# Serial.net
KiCad netlist of a schematic drawn in Altium Designer
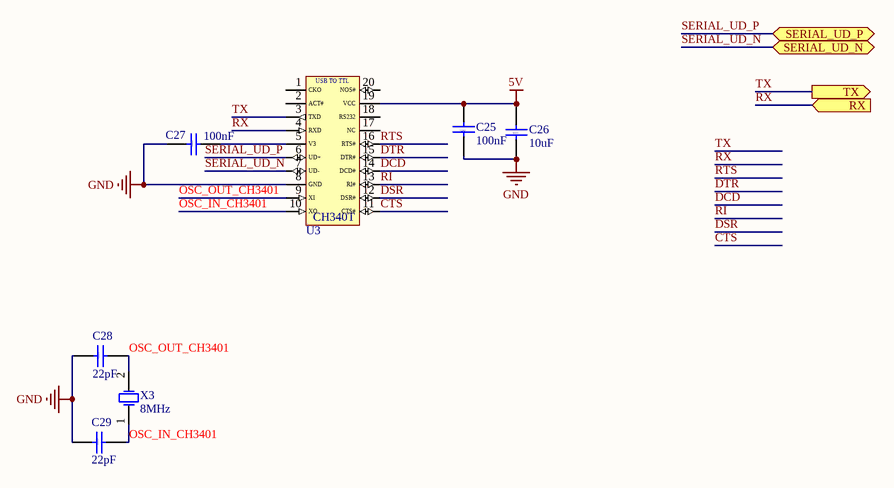
[diagram p0: Serial.SchDoc]

(export (version "E")
  (design (tool "Eeschema 10.0.6"))
  (components
    (comp (ref "C25")
      (value "100nF")
      (footprint "RES 0805")
      (libsource (lib "Full lib F.kh-V2") (part "CAP 0805"))
    )
    (comp (ref "C26")
      (value "10uF")
      (footprint "Res 1206")
      (libsource (lib "Full lib F.kh-V2") (part "CAP 1206"))
    )
    (comp (ref "C27")
      (value "100nF")
      (footprint "RES 0805")
      (libsource (lib "Full lib F.kh-V2") (part "CAP 0805"))
    )
    (comp (ref "C28")
      (value "22pF")
      (footprint "RES 0805")
      (libsource (lib "Full lib F.kh-V2") (part "CAP 0805"))
    )
    (comp (ref "C29")
      (value "22pF")
      (footprint "RES 0805")
      (libsource (lib "Full lib F.kh-V2") (part "CAP 0805"))
    )
    (comp (ref "U3")
      (value "CH340")
      (footprint "SSOP20")
      (description "USB to serial chip CH340")
      (libsource (lib "Full lib F.kh-V2") (part "CH340T"))
    )
    (comp (ref "X3")
      (value "8MHz")
      (footprint "XTAL - SMD")
      (libsource (lib "Full lib F.kh-V2") (part "XTAL - SMD"))
    )
  )
  (nets
    (net (code "1") (name "/CTS") (class "Default")
      (node (ref "U3") (pin "11") (pinfunction "CTS#_11") (pintype "bidirectional"))
    )
    (net (code "2") (name "/DCD") (class "Default")
      (node (ref "U3") (pin "14") (pinfunction "DCD#_14") (pintype "bidirectional"))
    )
    (net (code "3") (name "/DSR") (class "Default")
      (node (ref "U3") (pin "12") (pinfunction "DSR#_12") (pintype "bidirectional"))
    )
    (net (code "4") (name "/DTR") (class "Default")
      (node (ref "U3") (pin "15") (pinfunction "DTR#_15") (pintype "bidirectional"))
    )
    (net (code "5") (name "/OSC_IN_CH3401") (class "Default")
      (node (ref "C29") (pin "2") (pinfunction "2_2") (pintype "passive"))
      (node (ref "U3") (pin "10") (pinfunction "XO_10") (pintype "input"))
      (node (ref "X3") (pin "1") (pinfunction "OSC1_1") (pintype "passive"))
    )
    (net (code "6") (name "/OSC_OUT_CH3401") (class "Default")
      (node (ref "C28") (pin "2") (pinfunction "2_2") (pintype "passive"))
      (node (ref "U3") (pin "9") (pinfunction "XI_9") (pintype "input"))
      (node (ref "X3") (pin "2") (pinfunction "OSC2_2") (pintype "passive"))
    )
    (net (code "7") (name "/RI") (class "Default")
      (node (ref "U3") (pin "13") (pinfunction "RI#_13") (pintype "bidirectional"))
    )
    (net (code "8") (name "/RTS") (class "Default")
      (node (ref "U3") (pin "16") (pinfunction "RTS#_16") (pintype "bidirectional"))
    )
    (net (code "9") (name "/RX") (class "Default")
      (node (ref "U3") (pin "4") (pinfunction "RXD_4") (pintype "input"))
    )
    (net (code "10") (name "/SERIAL_UD_N") (class "Default")
      (node (ref "U3") (pin "7") (pinfunction "UD-_7") (pintype "bidirectional"))
    )
    (net (code "11") (name "/SERIAL_UD_P") (class "Default")
      (node (ref "U3") (pin "6") (pinfunction "UD+_6") (pintype "bidirectional"))
    )
    (net (code "12") (name "/TX") (class "Default")
      (node (ref "U3") (pin "3") (pinfunction "TXD_3") (pintype "output"))
    )
    (net (code "13") (name "5V") (class "Default")
      (node (ref "C25") (pin "2") (pinfunction "2_2") (pintype "passive"))
      (node (ref "C26") (pin "2") (pinfunction "2_2") (pintype "passive"))
      (node (ref "U3") (pin "19") (pinfunction "VCC_19") (pintype "power_in"))
    )
    (net (code "14") (name "GND") (class "Default")
      (node (ref "C25") (pin "1") (pinfunction "1_1") (pintype "passive"))
      (node (ref "C26") (pin "1") (pinfunction "1_1") (pintype "passive"))
      (node (ref "C27") (pin "1") (pinfunction "1_1") (pintype "passive"))
      (node (ref "C28") (pin "1") (pinfunction "1_1") (pintype "passive"))
      (node (ref "C29") (pin "1") (pinfunction "1_1") (pintype "passive"))
      (node (ref "U3") (pin "8") (pinfunction "GND_8") (pintype "power_in"))
    )
    (net (code "15") (name "Net-(U3-V3)") (class "Default")
      (node (ref "C27") (pin "2") (pinfunction "2_2") (pintype "passive"))
      (node (ref "U3") (pin "5") (pinfunction "V3_5") (pintype "power_in"))
    )
    (net (code "16") (name "unconnected-(U3-ACT#-Pad2)") (class "Default")
      (node (ref "U3") (pin "2") (pinfunction "ACT#_2") (pintype "power_in"))
    )
    (net (code "17") (name "unconnected-(U3-CKO-Pad1)") (class "Default")
      (node (ref "U3") (pin "1") (pinfunction "CKO_1") (pintype "passive"))
    )
    (net (code "18") (name "unconnected-(U3-NC-Pad17)") (class "Default")
      (node (ref "U3") (pin "17") (pinfunction "NC_17") (pintype "passive"))
    )
    (net (code "19") (name "unconnected-(U3-NOS#-Pad20)") (class "Default")
      (node (ref "U3") (pin "20") (pinfunction "NOS#_20") (pintype "bidirectional"))
    )
    (net (code "20") (name "unconnected-(U3-RS232-Pad18)") (class "Default")
      (node (ref "U3") (pin "18") (pinfunction "RS232_18") (pintype "passive"))
    )
  )
)
